# 4_bootleg-1-periferals.net
KiCad netlist of a schematic drawn in Altium Designer
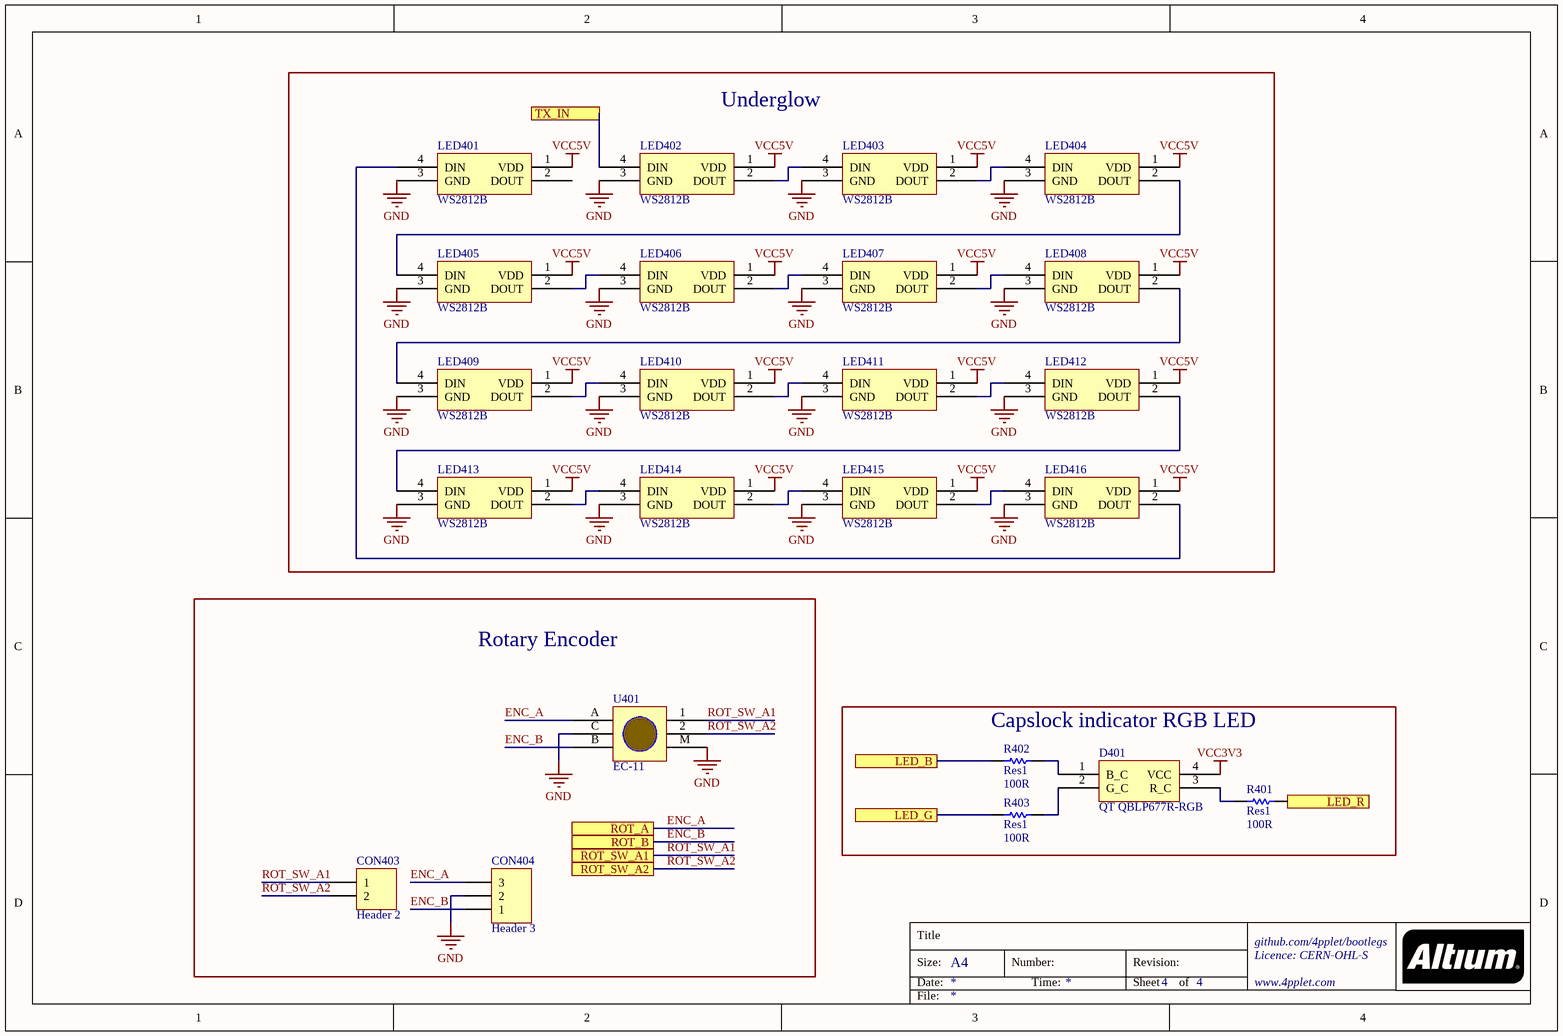
[diagram p0: 4_bootleg-1-periferals.SchDoc]

(export (version "E")
  (design (tool "Eeschema 10.0.6"))
  (components
    (comp (ref "CON403")
      (value "Header 2")
      (footprint "HDR1X2")
      (description "Header, 2-Pin")
      (libsource (lib "Miscellaneous Connectors") (part "Header 2"))
    )
    (comp (ref "CON404")
      (value "Header 3")
      (footprint "HDR1X3")
      (description "Header, 3-Pin")
      (libsource (lib "Miscellaneous Connectors") (part "Header 3"))
    )
    (comp (ref "D401")
      (value "QT QBLP677R-RGB")
      (footprint "QT QBLP677R-RGB")
      (description "RGB LED")
      (fields (field (name "MFG") "QT Brightek (QTB)"))
      (libsource (lib "Keebs") (part "QT QBLP677R-RGB"))
    )
    (comp (ref "LED401")
      (value "WS2812B")
      (footprint "WS2812B - 2020")
      (fields (field (name "LCSC PART #") "C965555") (field (name "MRF.PART") "WS2812B-2020"))
      (libsource (lib "Keebs") (part "WS2812B"))
    )
    (comp (ref "LED402")
      (value "WS2812B")
      (footprint "WS2812B - 2020")
      (fields (field (name "LCSC PART #") "C965555") (field (name "MRF.PART") "WS2812B-2020"))
      (libsource (lib "Keebs") (part "WS2812B"))
    )
    (comp (ref "LED403")
      (value "WS2812B")
      (footprint "WS2812B - 2020")
      (fields (field (name "LCSC PART #") "C965555") (field (name "MRF.PART") "WS2812B-2020"))
      (libsource (lib "Keebs") (part "WS2812B"))
    )
    (comp (ref "LED404")
      (value "WS2812B")
      (footprint "WS2812B - 2020")
      (fields (field (name "LCSC PART #") "C965555") (field (name "MRF.PART") "WS2812B-2020"))
      (libsource (lib "Keebs") (part "WS2812B"))
    )
    (comp (ref "LED405")
      (value "WS2812B")
      (footprint "WS2812B - 2020")
      (fields (field (name "LCSC PART #") "C965555") (field (name "MRF.PART") "WS2812B-2020"))
      (libsource (lib "Keebs") (part "WS2812B"))
    )
    (comp (ref "LED406")
      (value "WS2812B")
      (footprint "WS2812B - 2020")
      (fields (field (name "LCSC PART #") "C965555") (field (name "MRF.PART") "WS2812B-2020"))
      (libsource (lib "Keebs") (part "WS2812B"))
    )
    (comp (ref "LED407")
      (value "WS2812B")
      (footprint "WS2812B - 2020")
      (fields (field (name "LCSC PART #") "C965555") (field (name "MRF.PART") "WS2812B-2020"))
      (libsource (lib "Keebs") (part "WS2812B"))
    )
    (comp (ref "LED408")
      (value "WS2812B")
      (footprint "WS2812B - 2020")
      (fields (field (name "LCSC PART #") "C965555") (field (name "MRF.PART") "WS2812B-2020"))
      (libsource (lib "Keebs") (part "WS2812B"))
    )
    (comp (ref "LED409")
      (value "WS2812B")
      (footprint "WS2812B - 2020")
      (fields (field (name "LCSC PART #") "C965555") (field (name "MRF.PART") "WS2812B-2020"))
      (libsource (lib "Keebs") (part "WS2812B"))
    )
    (comp (ref "LED410")
      (value "WS2812B")
      (footprint "WS2812B - 2020")
      (fields (field (name "LCSC PART #") "C965555") (field (name "MRF.PART") "WS2812B-2020"))
      (libsource (lib "Keebs") (part "WS2812B"))
    )
    (comp (ref "LED411")
      (value "WS2812B")
      (footprint "WS2812B - 2020")
      (fields (field (name "LCSC PART #") "C965555") (field (name "MRF.PART") "WS2812B-2020"))
      (libsource (lib "Keebs") (part "WS2812B"))
    )
    (comp (ref "LED412")
      (value "WS2812B")
      (footprint "WS2812B - 2020")
      (fields (field (name "LCSC PART #") "C965555") (field (name "MRF.PART") "WS2812B-2020"))
      (libsource (lib "Keebs") (part "WS2812B"))
    )
    (comp (ref "LED413")
      (value "WS2812B")
      (footprint "WS2812B - 2020")
      (fields (field (name "LCSC PART #") "C965555") (field (name "MRF.PART") "WS2812B-2020"))
      (libsource (lib "Keebs") (part "WS2812B"))
    )
    (comp (ref "LED414")
      (value "WS2812B")
      (footprint "WS2812B - 2020")
      (fields (field (name "LCSC PART #") "C965555") (field (name "MRF.PART") "WS2812B-2020"))
      (libsource (lib "Keebs") (part "WS2812B"))
    )
    (comp (ref "LED415")
      (value "WS2812B")
      (footprint "WS2812B - 2020")
      (fields (field (name "LCSC PART #") "C965555") (field (name "MRF.PART") "WS2812B-2020"))
      (libsource (lib "Keebs") (part "WS2812B"))
    )
    (comp (ref "LED416")
      (value "WS2812B")
      (footprint "WS2812B - 2020")
      (fields (field (name "LCSC PART #") "C965555") (field (name "MRF.PART") "WS2812B-2020"))
      (libsource (lib "Keebs") (part "WS2812B"))
    )
    (comp (ref "R401")
      (value "Res1")
      (footprint "R0603[1608]")
      (description "Resistor")
      (fields
        (field (name "ALTIUM_VALUE") "100R")
        (field (name "LCSC PART #") "C22775")
        (field (name "MRF.PART") "0603WAF1000T5E")
      )
      (libsource (lib "Miscellaneous Devices") (part "Res1"))
    )
    (comp (ref "R402")
      (value "Res1")
      (footprint "R0603[1608]")
      (description "Resistor")
      (fields
        (field (name "ALTIUM_VALUE") "100R")
        (field (name "LCSC PART #") "C22775")
        (field (name "MRF.PART") "0603WAF1000T5E")
      )
      (libsource (lib "Miscellaneous Devices") (part "Res1"))
    )
    (comp (ref "R403")
      (value "Res1")
      (footprint "R0603[1608]")
      (description "Resistor")
      (fields
        (field (name "ALTIUM_VALUE") "100R")
        (field (name "LCSC PART #") "C22775")
        (field (name "MRF.PART") "0603WAF1000T5E")
      )
      (libsource (lib "Miscellaneous Devices") (part "Res1"))
    )
    (comp (ref "U401") (value "EC-11") (footprint "EC11-SMD") (libsource (lib "Keebs") (part "EC-11")))
  )
  (nets
    (net (code "1") (name "/ENC_A") (class "Default")
      (node (ref "CON404") (pin "3") (pinfunction "3_3") (pintype "passive"))
      (node (ref "U401") (pin "A") (pinfunction "B_A") (pintype "passive"))
    )
    (net (code "2") (name "/ENC_B") (class "Default")
      (node (ref "CON404") (pin "1") (pinfunction "1_1") (pintype "passive"))
      (node (ref "U401") (pin "B") (pinfunction "B_B") (pintype "passive"))
    )
    (net (code "3") (name "/LED_B") (class "Default")
      (node (ref "R402") (pin "2") (pinfunction "2_2") (pintype "passive"))
    )
    (net (code "4") (name "/LED_G") (class "Default")
      (node (ref "R403") (pin "2") (pinfunction "2_2") (pintype "passive"))
    )
    (net (code "5") (name "/LED_R") (class "Default")
      (node (ref "R401") (pin "1") (pinfunction "1_1") (pintype "passive"))
    )
    (net (code "6") (name "/ROT_SW_A1") (class "Default")
      (node (ref "CON403") (pin "1") (pinfunction "1_1") (pintype "passive"))
      (node (ref "U401") (pin "1") (pinfunction "1_1") (pintype "passive"))
    )
    (net (code "7") (name "/ROT_SW_A2") (class "Default")
      (node (ref "CON403") (pin "2") (pinfunction "2_2") (pintype "passive"))
      (node (ref "U401") (pin "2") (pinfunction "2_2") (pintype "passive"))
    )
    (net (code "8") (name "/TX_IN") (class "Default")
      (node (ref "LED402") (pin "4") (pinfunction "DIN_4") (pintype "passive"))
    )
    (net (code "9") (name "GND") (class "Default")
      (node (ref "CON404") (pin "2") (pinfunction "2_2") (pintype "passive"))
      (node (ref "LED401") (pin "3") (pinfunction "GND_3") (pintype "passive"))
      (node (ref "LED402") (pin "3") (pinfunction "GND_3") (pintype "passive"))
      (node (ref "LED403") (pin "3") (pinfunction "GND_3") (pintype "passive"))
      (node (ref "LED404") (pin "3") (pinfunction "GND_3") (pintype "passive"))
      (node (ref "LED405") (pin "3") (pinfunction "GND_3") (pintype "passive"))
      (node (ref "LED406") (pin "3") (pinfunction "GND_3") (pintype "passive"))
      (node (ref "LED407") (pin "3") (pinfunction "GND_3") (pintype "passive"))
      (node (ref "LED408") (pin "3") (pinfunction "GND_3") (pintype "passive"))
      (node (ref "LED409") (pin "3") (pinfunction "GND_3") (pintype "passive"))
      (node (ref "LED410") (pin "3") (pinfunction "GND_3") (pintype "passive"))
      (node (ref "LED411") (pin "3") (pinfunction "GND_3") (pintype "passive"))
      (node (ref "LED412") (pin "3") (pinfunction "GND_3") (pintype "passive"))
      (node (ref "LED413") (pin "3") (pinfunction "GND_3") (pintype "passive"))
      (node (ref "LED414") (pin "3") (pinfunction "GND_3") (pintype "passive"))
      (node (ref "LED415") (pin "3") (pinfunction "GND_3") (pintype "passive"))
      (node (ref "LED416") (pin "3") (pinfunction "GND_3") (pintype "passive"))
      (node (ref "U401") (pin "C") (pinfunction "C_C") (pintype "passive"))
      (node (ref "U401") (pin "M") (pinfunction "M_M") (pintype "passive"))
    )
    (net (code "10") (name "Net-(D401-B_C)") (class "Default")
      (node (ref "D401") (pin "1") (pinfunction "B_C_1") (pintype "passive"))
      (node (ref "R402") (pin "1") (pinfunction "1_1") (pintype "passive"))
    )
    (net (code "11") (name "Net-(D401-G_C)") (class "Default")
      (node (ref "D401") (pin "2") (pinfunction "G_C_2") (pintype "passive"))
      (node (ref "R403") (pin "1") (pinfunction "1_1") (pintype "passive"))
    )
    (net (code "12") (name "Net-(D401-R_C)") (class "Default")
      (node (ref "D401") (pin "3") (pinfunction "R_C_3") (pintype "passive"))
      (node (ref "R401") (pin "2") (pinfunction "2_2") (pintype "passive"))
    )
    (net (code "13") (name "Net-(LED401-DIN)") (class "Default")
      (node (ref "LED401") (pin "4") (pinfunction "DIN_4") (pintype "passive"))
      (node (ref "LED416") (pin "2") (pinfunction "DOUT_2") (pintype "passive"))
    )
    (net (code "14") (name "Net-(LED402-DOUT)") (class "Default")
      (node (ref "LED402") (pin "2") (pinfunction "DOUT_2") (pintype "passive"))
      (node (ref "LED403") (pin "4") (pinfunction "DIN_4") (pintype "passive"))
    )
    (net (code "15") (name "Net-(LED403-DOUT)") (class "Default")
      (node (ref "LED403") (pin "2") (pinfunction "DOUT_2") (pintype "passive"))
      (node (ref "LED404") (pin "4") (pinfunction "DIN_4") (pintype "passive"))
    )
    (net (code "16") (name "Net-(LED404-DOUT)") (class "Default")
      (node (ref "LED404") (pin "2") (pinfunction "DOUT_2") (pintype "passive"))
      (node (ref "LED405") (pin "4") (pinfunction "DIN_4") (pintype "passive"))
    )
    (net (code "17") (name "Net-(LED405-DOUT)") (class "Default")
      (node (ref "LED405") (pin "2") (pinfunction "DOUT_2") (pintype "passive"))
      (node (ref "LED406") (pin "4") (pinfunction "DIN_4") (pintype "passive"))
    )
    (net (code "18") (name "Net-(LED406-DOUT)") (class "Default")
      (node (ref "LED406") (pin "2") (pinfunction "DOUT_2") (pintype "passive"))
      (node (ref "LED407") (pin "4") (pinfunction "DIN_4") (pintype "passive"))
    )
    (net (code "19") (name "Net-(LED407-DOUT)") (class "Default")
      (node (ref "LED407") (pin "2") (pinfunction "DOUT_2") (pintype "passive"))
      (node (ref "LED408") (pin "4") (pinfunction "DIN_4") (pintype "passive"))
    )
    (net (code "20") (name "Net-(LED408-DOUT)") (class "Default")
      (node (ref "LED408") (pin "2") (pinfunction "DOUT_2") (pintype "passive"))
      (node (ref "LED409") (pin "4") (pinfunction "DIN_4") (pintype "passive"))
    )
    (net (code "21") (name "Net-(LED409-DOUT)") (class "Default")
      (node (ref "LED409") (pin "2") (pinfunction "DOUT_2") (pintype "passive"))
      (node (ref "LED410") (pin "4") (pinfunction "DIN_4") (pintype "passive"))
    )
    (net (code "22") (name "Net-(LED410-DOUT)") (class "Default")
      (node (ref "LED410") (pin "2") (pinfunction "DOUT_2") (pintype "passive"))
      (node (ref "LED411") (pin "4") (pinfunction "DIN_4") (pintype "passive"))
    )
    (net (code "23") (name "Net-(LED411-DOUT)") (class "Default")
      (node (ref "LED411") (pin "2") (pinfunction "DOUT_2") (pintype "passive"))
      (node (ref "LED412") (pin "4") (pinfunction "DIN_4") (pintype "passive"))
    )
    (net (code "24") (name "Net-(LED412-DOUT)") (class "Default")
      (node (ref "LED412") (pin "2") (pinfunction "DOUT_2") (pintype "passive"))
      (node (ref "LED413") (pin "4") (pinfunction "DIN_4") (pintype "passive"))
    )
    (net (code "25") (name "Net-(LED413-DOUT)") (class "Default")
      (node (ref "LED413") (pin "2") (pinfunction "DOUT_2") (pintype "passive"))
      (node (ref "LED414") (pin "4") (pinfunction "DIN_4") (pintype "passive"))
    )
    (net (code "26") (name "Net-(LED414-DOUT)") (class "Default")
      (node (ref "LED414") (pin "2") (pinfunction "DOUT_2") (pintype "passive"))
      (node (ref "LED415") (pin "4") (pinfunction "DIN_4") (pintype "passive"))
    )
    (net (code "27") (name "Net-(LED415-DOUT)") (class "Default")
      (node (ref "LED415") (pin "2") (pinfunction "DOUT_2") (pintype "passive"))
      (node (ref "LED416") (pin "4") (pinfunction "DIN_4") (pintype "passive"))
    )
    (net (code "28") (name "VCC3V3") (class "Default")
      (node (ref "D401") (pin "4") (pinfunction "VCC_4") (pintype "passive"))
    )
    (net (code "29") (name "VCC5V") (class "Default")
      (node (ref "LED401") (pin "1") (pinfunction "VDD_1") (pintype "passive"))
      (node (ref "LED402") (pin "1") (pinfunction "VDD_1") (pintype "passive"))
      (node (ref "LED403") (pin "1") (pinfunction "VDD_1") (pintype "passive"))
      (node (ref "LED404") (pin "1") (pinfunction "VDD_1") (pintype "passive"))
      (node (ref "LED405") (pin "1") (pinfunction "VDD_1") (pintype "passive"))
      (node (ref "LED406") (pin "1") (pinfunction "VDD_1") (pintype "passive"))
      (node (ref "LED407") (pin "1") (pinfunction "VDD_1") (pintype "passive"))
      (node (ref "LED408") (pin "1") (pinfunction "VDD_1") (pintype "passive"))
      (node (ref "LED409") (pin "1") (pinfunction "VDD_1") (pintype "passive"))
      (node (ref "LED410") (pin "1") (pinfunction "VDD_1") (pintype "passive"))
      (node (ref "LED411") (pin "1") (pinfunction "VDD_1") (pintype "passive"))
      (node (ref "LED412") (pin "1") (pinfunction "VDD_1") (pintype "passive"))
      (node (ref "LED413") (pin "1") (pinfunction "VDD_1") (pintype "passive"))
      (node (ref "LED414") (pin "1") (pinfunction "VDD_1") (pintype "passive"))
      (node (ref "LED415") (pin "1") (pinfunction "VDD_1") (pintype "passive"))
      (node (ref "LED416") (pin "1") (pinfunction "VDD_1") (pintype "passive"))
    )
    (net (code "30") (name "unconnected-(LED401-DOUT-Pad2)") (class "Default")
      (node (ref "LED401") (pin "2") (pinfunction "DOUT_2") (pintype "passive"))
    )
  )
)
